# BLE_V_1_0.net
KiCad netlist of a schematic drawn in EAGLE
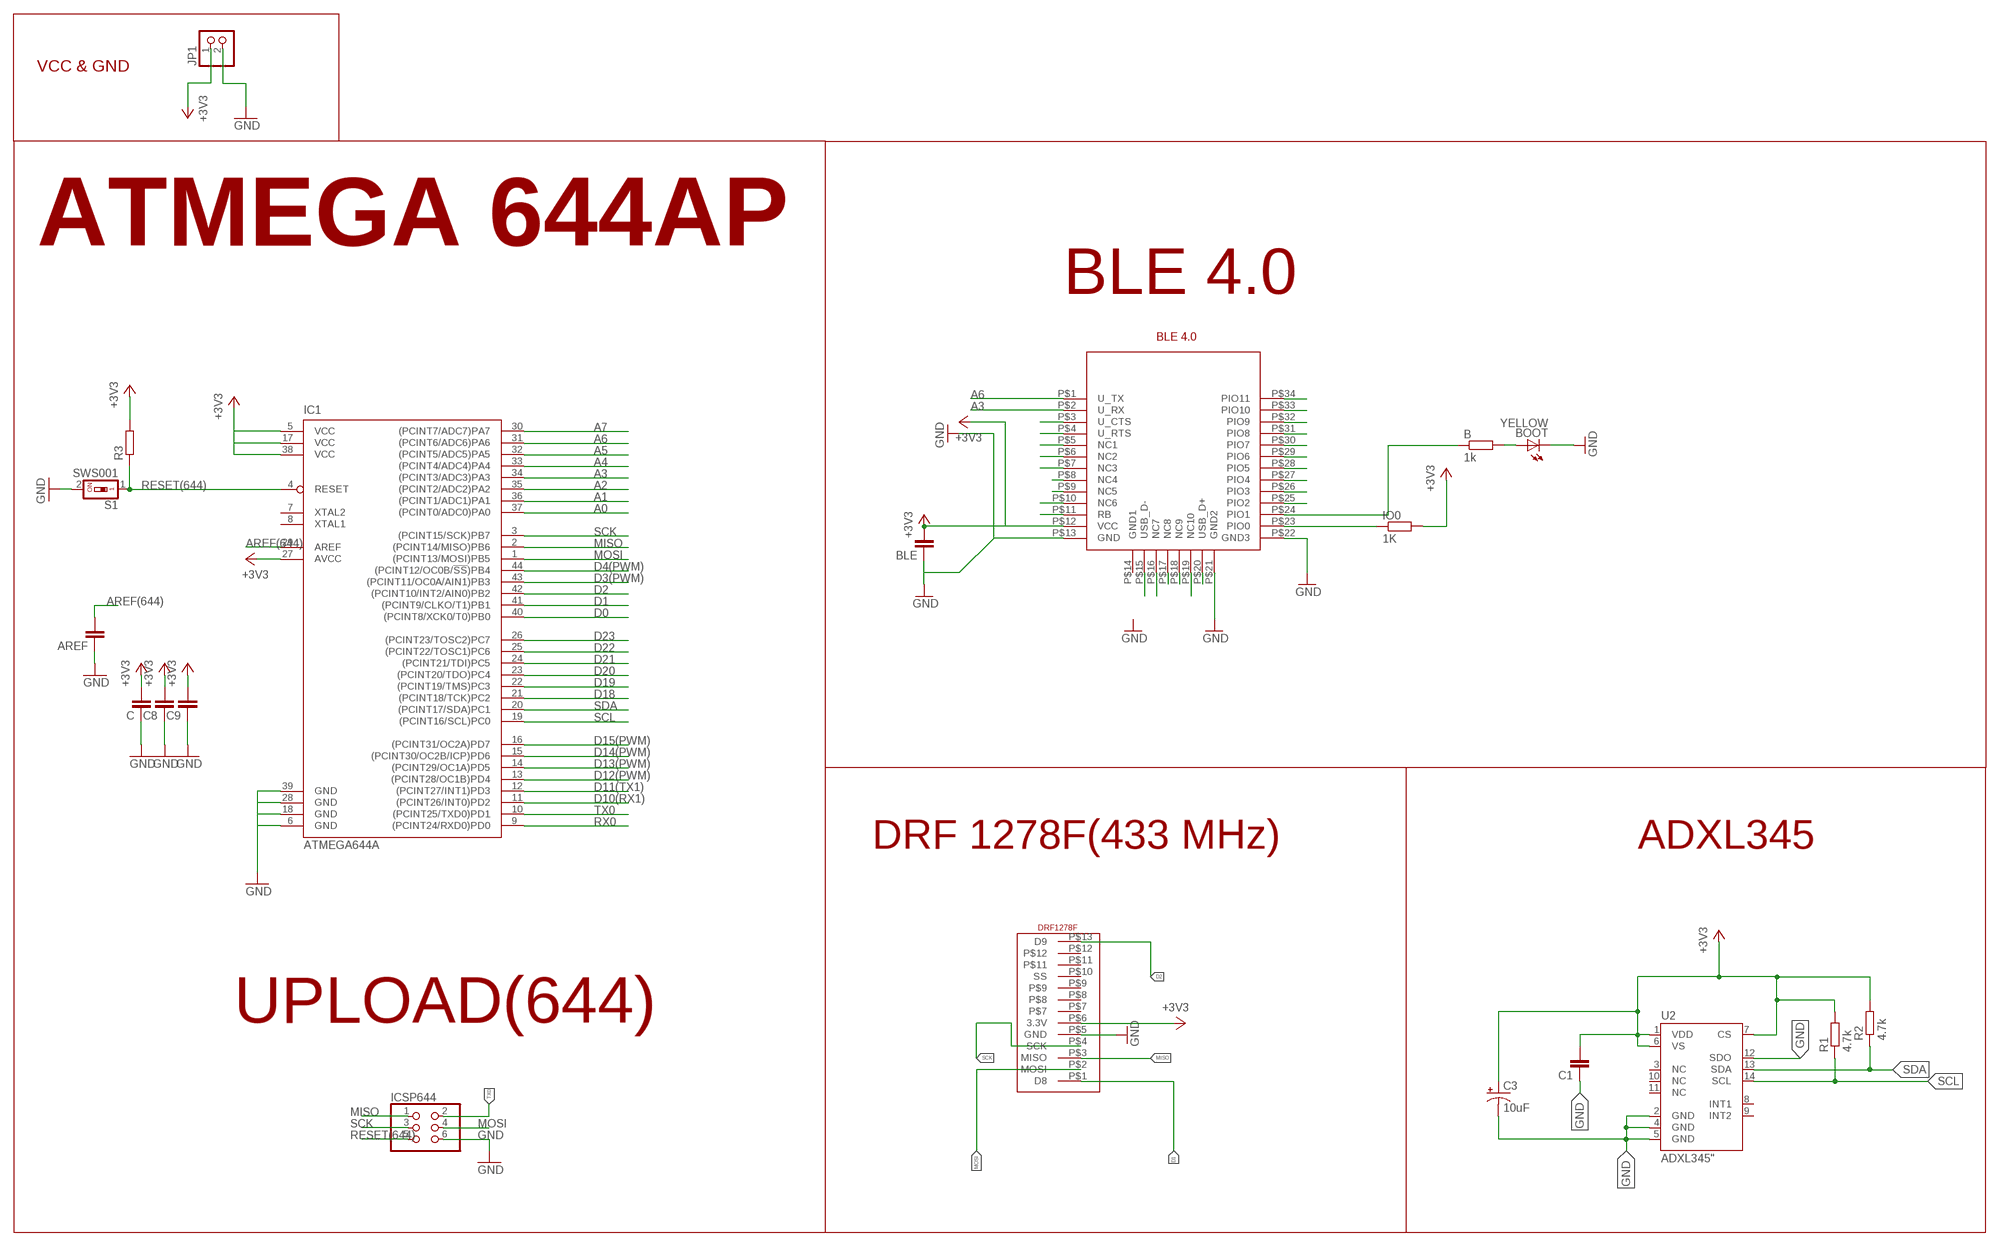
[diagram p0: schematic, sheet 1]

(export (version "E")
  (design (tool "Eeschema 10.0.6"))
  (components
    (comp (ref "AREF")
      (value "100nF")
      (footprint "eagle-import:C0805")
      (libsource (lib "eagle-import") (part "C-EUC0805"))
    )
    (comp (ref "B")
      (value "1k")
      (footprint "eagle-import:R0805")
      (libsource (lib "eagle-import") (part "R-EU_R0805"))
    )
    (comp (ref "BLE")
      (value "100nF")
      (footprint "eagle-import:C0805")
      (libsource (lib "eagle-import") (part "C-EUC0805"))
    )
    (comp (ref "BOOT")
      (value "YELLOW")
      (footprint "eagle-import:CHIP-LED0805")
      (libsource (lib "eagle-import") (part "LEDCHIP-LED0805"))
    )
    (comp (ref "C")
      (value "22 uF")
      (footprint "eagle-import:C0805")
      (libsource (lib "eagle-import") (part "C-EUC0805"))
    )
    (comp (ref "C1")
      (value "0.1uF")
      (footprint "eagle-import:C0805")
      (libsource (lib "eagle-import") (part "C-EUC0805"))
    )
    (comp (ref "C3")
      (value "10uF")
      (footprint "eagle-import:EIA3216")
      (libsource (lib "eagle-import") (part "CAP_POL1206"))
    )
    (comp (ref "C8")
      (value "100nF")
      (footprint "eagle-import:C0805")
      (libsource (lib "eagle-import") (part "C-EUC0805"))
    )
    (comp (ref "C9")
      (value "100nF")
      (footprint "eagle-import:C0805")
      (libsource (lib "eagle-import") (part "C-EUC0805"))
    )
    (comp (ref "IC1")
      (value "ATMEGA644A")
      (footprint "eagle-import:TQFP44")
      (fields (field (name "MPN") "ATMEGA644PV-10AU"))
      (libsource (lib "eagle-import") (part "ATMEGA644A"))
    )
    (comp (ref "ICSP644")
      (value "PINHD-2X3")
      (footprint "eagle-import:2X03")
      (libsource (lib "eagle-import") (part "PINHD-2X3"))
    )
    (comp (ref "IO0")
      (value "1K")
      (footprint "eagle-import:R0805")
      (libsource (lib "eagle-import") (part "R-EU_R0805"))
    )
    (comp (ref "JP1")
      (value "PINHD-1X2")
      (footprint "eagle-import:1X02")
      (libsource (lib "eagle-import") (part "PINHD-1X2"))
    )
    (comp (ref "R1")
      (value "4.7k")
      (footprint "eagle-import:R0805")
      (libsource (lib "eagle-import") (part "R-EU_R0805"))
    )
    (comp (ref "R2")
      (value "4.7k")
      (footprint "eagle-import:R0805")
      (libsource (lib "eagle-import") (part "R-EU_R0805"))
    )
    (comp (ref "R3")
      (value "R-EU_R0805")
      (footprint "eagle-import:R0805")
      (libsource (lib "eagle-import") (part "R-EU_R0805"))
    )
    (comp (ref "S1")
      (value "SWS001")
      (footprint "eagle-import:SMS-001")
      (libsource (lib "eagle-import") (part "SWS001"))
    )
    (comp (ref "U$1")
      (value "DRF1278F")
      (footprint "eagle-import:DIP13")
      (libsource (lib "eagle-import") (part "DRF1278F"))
    )
    (comp (ref "U$6")
      (value "BLUETOOTH_4.0(13)")
      (footprint "eagle-import:BLUTOOTH_4.0(13)")
      (libsource (lib "eagle-import") (part "BLUETOOTH_4.0(13)"))
    )
    (comp (ref "U2")
      (value "ADXL345\"")
      (footprint "eagle-import:ADXL3451_1")
      (libsource (lib "eagle-import") (part "ADXL345{dblquote}"))
    )
  )
  (nets
    (net (code "1") (name "+3V3") (class "Default")
      (node (ref "BLE") (pin "2") (pinfunction "2_2") (pintype "passive"))
      (node (ref "C") (pin "2") (pinfunction "2_2") (pintype "passive"))
      (node (ref "C1") (pin "2") (pinfunction "2_2") (pintype "passive"))
      (node (ref "C3") (pin "A") (pinfunction "+_A") (pintype "passive"))
      (node (ref "C8") (pin "2") (pinfunction "2_2") (pintype "passive"))
      (node (ref "C9") (pin "2") (pinfunction "2_2") (pintype "passive"))
      (node (ref "IC1") (pin "17") (pinfunction "VCC_17") (pintype "power_in"))
      (node (ref "IC1") (pin "27") (pinfunction "AVCC_27") (pintype "power_in"))
      (node (ref "IC1") (pin "38") (pinfunction "VCC_38") (pintype "power_in"))
      (node (ref "IC1") (pin "5") (pinfunction "VCC_5") (pintype "power_in"))
      (node (ref "IO0") (pin "2") (pinfunction "2_2") (pintype "passive"))
      (node (ref "JP1") (pin "1") (pinfunction "1_1") (pintype "passive"))
      (node (ref "R1") (pin "2") (pinfunction "2_2") (pintype "passive"))
      (node (ref "R2") (pin "2") (pinfunction "2_2") (pintype "passive"))
      (node (ref "R3") (pin "2") (pinfunction "2_2") (pintype "passive"))
      (node (ref "U$1") (pin "P$6") (pinfunction "3.3V_P$6") (pintype "bidirectional"))
      (node (ref "U$6") (pin "P$12") (pinfunction "VCC_P$12") (pintype "bidirectional"))
      (node (ref "U2") (pin "1") (pinfunction "VDD_1") (pintype "bidirectional"))
      (node (ref "U2") (pin "6") (pinfunction "VS_6") (pintype "bidirectional"))
      (node (ref "U2") (pin "7") (pinfunction "CS_7") (pintype "bidirectional"))
    )
    (net (code "2") (name "/A0") (class "Default")
      (node (ref "IC1") (pin "37") (pinfunction "(PCINT0/ADC0)PA0_37") (pintype "bidirectional"))
    )
    (net (code "3") (name "/A1") (class "Default")
      (node (ref "IC1") (pin "36") (pinfunction "(PCINT1/ADC1)PA1_36") (pintype "bidirectional"))
    )
    (net (code "4") (name "/A2") (class "Default")
      (node (ref "IC1") (pin "35") (pinfunction "(PCINT2/ADC2)PA2_35") (pintype "bidirectional"))
    )
    (net (code "5") (name "/A3") (class "Default")
      (node (ref "IC1") (pin "34") (pinfunction "(PCINT3/ADC3)PA3_34") (pintype "bidirectional"))
      (node (ref "U$6") (pin "P$2") (pinfunction "U_RX_P$2") (pintype "bidirectional"))
    )
    (net (code "6") (name "/A4") (class "Default")
      (node (ref "IC1") (pin "33") (pinfunction "(PCINT4/ADC4)PA4_33") (pintype "bidirectional"))
    )
    (net (code "7") (name "/A5") (class "Default")
      (node (ref "IC1") (pin "32") (pinfunction "(PCINT5/ADC5)PA5_32") (pintype "bidirectional"))
    )
    (net (code "8") (name "/A6") (class "Default")
      (node (ref "IC1") (pin "31") (pinfunction "(PCINT6/ADC6)PA6_31") (pintype "bidirectional"))
      (node (ref "U$6") (pin "P$1") (pinfunction "U_TX_P$1") (pintype "bidirectional"))
    )
    (net (code "9") (name "/A7") (class "Default")
      (node (ref "IC1") (pin "30") (pinfunction "(PCINT7/ADC7)PA7_30") (pintype "bidirectional"))
    )
    (net (code "10") (name "/AREF(644)") (class "Default")
      (node (ref "AREF") (pin "2") (pinfunction "2_2") (pintype "passive"))
      (node (ref "IC1") (pin "29") (pinfunction "AREF_29") (pintype "passive"))
    )
    (net (code "11") (name "/D0") (class "Default")
      (node (ref "IC1") (pin "40") (pinfunction "(PCINT8/XCK0/T0)PB0_40") (pintype "bidirectional"))
    )
    (net (code "12") (name "/D3(PWM)") (class "Default")
      (node (ref "IC1") (pin "43") (pinfunction "(PCINT11/OC0A/AIN1)PB3_43") (pintype "bidirectional"))
    )
    (net (code "13") (name "/D4(PWM)") (class "Default")
      (node (ref "IC1") (pin "44") (pinfunction "(PCINT12/OC0B/~{SS})PB4_44") (pintype "bidirectional"))
    )
    (net (code "14") (name "/D10(RX1)") (class "Default")
      (node (ref "IC1") (pin "11") (pinfunction "(PCINT26/INT0)PD2_11") (pintype "bidirectional"))
    )
    (net (code "15") (name "/D11(TX1)") (class "Default")
      (node (ref "IC1") (pin "12") (pinfunction "(PCINT27/INT1)PD3_12") (pintype "bidirectional"))
    )
    (net (code "16") (name "/D12(PWM)") (class "Default")
      (node (ref "IC1") (pin "13") (pinfunction "(PCINT28/OC1B)PD4_13") (pintype "bidirectional"))
    )
    (net (code "17") (name "/D13(PWM)") (class "Default")
      (node (ref "IC1") (pin "14") (pinfunction "(PCINT29/OC1A)PD5_14") (pintype "bidirectional"))
    )
    (net (code "18") (name "/D14(PWM)") (class "Default")
      (node (ref "IC1") (pin "15") (pinfunction "(PCINT30/OC2B/ICP)PD6_15") (pintype "bidirectional"))
    )
    (net (code "19") (name "/D15(PWM)") (class "Default")
      (node (ref "IC1") (pin "16") (pinfunction "(PCINT31/OC2A)PD7_16") (pintype "bidirectional"))
    )
    (net (code "20") (name "/D18") (class "Default")
      (node (ref "IC1") (pin "21") (pinfunction "(PCINT18/TCK)PC2_21") (pintype "output"))
    )
    (net (code "21") (name "/D19") (class "Default")
      (node (ref "IC1") (pin "22") (pinfunction "(PCINT19/TMS)PC3_22") (pintype "output"))
    )
    (net (code "22") (name "/D20") (class "Default")
      (node (ref "IC1") (pin "23") (pinfunction "(PCINT20/TDO)PC4_23") (pintype "output"))
    )
    (net (code "23") (name "/D21") (class "Default")
      (node (ref "IC1") (pin "24") (pinfunction "(PCINT21/TDI)PC5_24") (pintype "output"))
    )
    (net (code "24") (name "/D22") (class "Default")
      (node (ref "IC1") (pin "25") (pinfunction "(PCINT22/TOSC1)PC6_25") (pintype "output"))
    )
    (net (code "25") (name "/D23") (class "Default")
      (node (ref "IC1") (pin "26") (pinfunction "(PCINT23/TOSC2)PC7_26") (pintype "output"))
    )
    (net (code "26") (name "/RESET(644)") (class "Default")
      (node (ref "IC1") (pin "4") (pinfunction "RESET_4") (pintype "input"))
      (node (ref "ICSP644") (pin "5") (pinfunction "5_5") (pintype "passive"))
      (node (ref "R3") (pin "1") (pinfunction "1_1") (pintype "passive"))
      (node (ref "S1") (pin "1") (pinfunction "1_1") (pintype "passive"))
    )
    (net (code "27") (name "/RX0") (class "Default")
      (node (ref "IC1") (pin "9") (pinfunction "(PCINT24/RXD0)PD0_9") (pintype "bidirectional"))
    )
    (net (code "28") (name "D1") (class "Default")
      (node (ref "IC1") (pin "41") (pinfunction "(PCINT9/CLKO/T1)PB1_41") (pintype "bidirectional"))
      (node (ref "U$1") (pin "P$1") (pinfunction "D8_P$1") (pintype "bidirectional"))
    )
    (net (code "29") (name "D2") (class "Default")
      (node (ref "IC1") (pin "42") (pinfunction "(PCINT10/INT2/AIN0)PB2_42") (pintype "bidirectional"))
      (node (ref "U$1") (pin "P$13") (pinfunction "D9_P$13") (pintype "bidirectional"))
    )
    (net (code "30") (name "GND") (class "Default")
      (node (ref "AREF") (pin "1") (pinfunction "1_1") (pintype "passive"))
      (node (ref "BLE") (pin "1") (pinfunction "1_1") (pintype "passive"))
      (node (ref "BOOT") (pin "C") (pinfunction "C_C") (pintype "passive"))
      (node (ref "C") (pin "1") (pinfunction "1_1") (pintype "passive"))
      (node (ref "C1") (pin "1") (pinfunction "1_1") (pintype "passive"))
      (node (ref "C3") (pin "C") (pinfunction "-_C") (pintype "passive"))
      (node (ref "C8") (pin "1") (pinfunction "1_1") (pintype "passive"))
      (node (ref "C9") (pin "1") (pinfunction "1_1") (pintype "passive"))
      (node (ref "IC1") (pin "18") (pinfunction "GND_18") (pintype "power_in"))
      (node (ref "IC1") (pin "28") (pinfunction "GND_28") (pintype "power_in"))
      (node (ref "IC1") (pin "39") (pinfunction "GND_39") (pintype "power_in"))
      (node (ref "IC1") (pin "6") (pinfunction "GND_6") (pintype "power_in"))
      (node (ref "ICSP644") (pin "6") (pinfunction "6_6") (pintype "passive"))
      (node (ref "JP1") (pin "2") (pinfunction "2_2") (pintype "passive"))
      (node (ref "S1") (pin "2") (pinfunction "2_2") (pintype "passive"))
      (node (ref "U$1") (pin "P$5") (pinfunction "GND_P$5") (pintype "bidirectional"))
      (node (ref "U$6") (pin "P$13") (pinfunction "GND_P$13") (pintype "bidirectional"))
      (node (ref "U$6") (pin "P$21") (pinfunction "GND2_P$21") (pintype "bidirectional"))
      (node (ref "U$6") (pin "P$22") (pinfunction "GND3_P$22") (pintype "bidirectional"))
      (node (ref "U2") (pin "12") (pinfunction "SDO_12") (pintype "bidirectional"))
      (node (ref "U2") (pin "2") (pinfunction "GND_2") (pintype "bidirectional"))
      (node (ref "U2") (pin "4") (pinfunction "GND_4") (pintype "bidirectional"))
      (node (ref "U2") (pin "5") (pinfunction "GND_5") (pintype "bidirectional"))
    )
    (net (code "31") (name "MISO") (class "Default")
      (node (ref "IC1") (pin "2") (pinfunction "(PCINT14/MISO)PB6_2") (pintype "bidirectional"))
      (node (ref "ICSP644") (pin "1") (pinfunction "1_1") (pintype "passive"))
      (node (ref "U$1") (pin "P$3") (pinfunction "MISO_P$3") (pintype "bidirectional"))
    )
    (net (code "32") (name "MOSI") (class "Default")
      (node (ref "IC1") (pin "1") (pinfunction "(PCINT13/MOSI)PB5_1") (pintype "bidirectional"))
      (node (ref "ICSP644") (pin "4") (pinfunction "4_4") (pintype "passive"))
      (node (ref "U$1") (pin "P$2") (pinfunction "MOSI_P$2") (pintype "bidirectional"))
    )
    (net (code "33") (name "Net-(B-Pad2)") (class "Default")
      (node (ref "B") (pin "2") (pinfunction "2_2") (pintype "passive"))
      (node (ref "BOOT") (pin "A") (pinfunction "A_A") (pintype "passive"))
    )
    (net (code "34") (name "Net-(U$6-PIO0)") (class "Default")
      (node (ref "IO0") (pin "1") (pinfunction "1_1") (pintype "passive"))
      (node (ref "U$6") (pin "P$23") (pinfunction "PIO0_P$23") (pintype "bidirectional"))
    )
    (net (code "35") (name "Net-(U$6-PIO1)") (class "Default")
      (node (ref "B") (pin "1") (pinfunction "1_1") (pintype "passive"))
      (node (ref "U$6") (pin "P$24") (pinfunction "PIO1_P$24") (pintype "bidirectional"))
    )
    (net (code "36") (name "SCK") (class "Default")
      (node (ref "IC1") (pin "3") (pinfunction "(PCINT15/SCK)PB7_3") (pintype "bidirectional"))
      (node (ref "ICSP644") (pin "3") (pinfunction "3_3") (pintype "passive"))
      (node (ref "U$1") (pin "P$4") (pinfunction "SCK_P$4") (pintype "bidirectional"))
    )
    (net (code "37") (name "SCL") (class "Default")
      (node (ref "IC1") (pin "19") (pinfunction "(PCINT16/SCL)PC0_19") (pintype "output"))
      (node (ref "R1") (pin "1") (pinfunction "1_1") (pintype "passive"))
      (node (ref "U2") (pin "14") (pinfunction "SCL_14") (pintype "bidirectional"))
    )
    (net (code "38") (name "SDA") (class "Default")
      (node (ref "IC1") (pin "20") (pinfunction "(PCINT17/SDA)PC1_20") (pintype "output"))
      (node (ref "R2") (pin "1") (pinfunction "1_1") (pintype "passive"))
      (node (ref "U2") (pin "13") (pinfunction "SDA_13") (pintype "bidirectional"))
    )
    (net (code "39") (name "TX0") (class "Default")
      (node (ref "IC1") (pin "10") (pinfunction "(PCINT25/TXD0)PD1_10") (pintype "bidirectional"))
      (node (ref "ICSP644") (pin "2") (pinfunction "2_2") (pintype "passive"))
    )
    (net (code "40") (name "unconnected-(IC1-XTAL1-Pad8)") (class "Default")
      (node (ref "IC1") (pin "8") (pinfunction "XTAL1_8") (pintype "bidirectional"))
    )
    (net (code "41") (name "unconnected-(IC1-XTAL2-Pad7)") (class "Default")
      (node (ref "IC1") (pin "7") (pinfunction "XTAL2_7") (pintype "bidirectional"))
    )
    (net (code "42") (name "unconnected-(U$1-PadP$7)") (class "Default")
      (node (ref "U$1") (pin "P$7") (pinfunction "P$7_P$7") (pintype "bidirectional"))
    )
    (net (code "43") (name "unconnected-(U$1-PadP$8)") (class "Default")
      (node (ref "U$1") (pin "P$8") (pinfunction "P$8_P$8") (pintype "bidirectional"))
    )
    (net (code "44") (name "unconnected-(U$1-PadP$9)") (class "Default")
      (node (ref "U$1") (pin "P$9") (pinfunction "P$9_P$9") (pintype "bidirectional"))
    )
    (net (code "45") (name "unconnected-(U$1-PadP$11)") (class "Default")
      (node (ref "U$1") (pin "P$11") (pinfunction "P$11_P$11") (pintype "bidirectional"))
    )
    (net (code "46") (name "unconnected-(U$1-PadP$12)") (class "Default")
      (node (ref "U$1") (pin "P$12") (pinfunction "P$12_P$12") (pintype "bidirectional"))
    )
    (net (code "47") (name "unconnected-(U$1-SS-PadP$10)") (class "Default")
      (node (ref "U$1") (pin "P$10") (pinfunction "SS_P$10") (pintype "bidirectional"))
    )
    (net (code "48") (name "unconnected-(U$6-GND1-PadP$14)") (class "Default")
      (node (ref "U$6") (pin "P$14") (pinfunction "GND1_P$14") (pintype "bidirectional"))
    )
    (net (code "49") (name "unconnected-(U$6-NC1-PadP$5)") (class "Default")
      (node (ref "U$6") (pin "P$5") (pinfunction "NC1_P$5") (pintype "bidirectional"))
    )
    (net (code "50") (name "unconnected-(U$6-NC2-PadP$6)") (class "Default")
      (node (ref "U$6") (pin "P$6") (pinfunction "NC2_P$6") (pintype "bidirectional"))
    )
    (net (code "51") (name "unconnected-(U$6-NC3-PadP$7)") (class "Default")
      (node (ref "U$6") (pin "P$7") (pinfunction "NC3_P$7") (pintype "bidirectional"))
    )
    (net (code "52") (name "unconnected-(U$6-NC4-PadP$8)") (class "Default")
      (node (ref "U$6") (pin "P$8") (pinfunction "NC4_P$8") (pintype "bidirectional"))
    )
    (net (code "53") (name "unconnected-(U$6-NC5-PadP$9)") (class "Default")
      (node (ref "U$6") (pin "P$9") (pinfunction "NC5_P$9") (pintype "bidirectional"))
    )
    (net (code "54") (name "unconnected-(U$6-NC6-PadP$10)") (class "Default")
      (node (ref "U$6") (pin "P$10") (pinfunction "NC6_P$10") (pintype "bidirectional"))
    )
    (net (code "55") (name "unconnected-(U$6-NC7-PadP$16)") (class "Default")
      (node (ref "U$6") (pin "P$16") (pinfunction "NC7_P$16") (pintype "bidirectional"))
    )
    (net (code "56") (name "unconnected-(U$6-NC8-PadP$17)") (class "Default")
      (node (ref "U$6") (pin "P$17") (pinfunction "NC8_P$17") (pintype "bidirectional"))
    )
    (net (code "57") (name "unconnected-(U$6-NC9-PadP$18)") (class "Default")
      (node (ref "U$6") (pin "P$18") (pinfunction "NC9_P$18") (pintype "bidirectional"))
    )
    (net (code "58") (name "unconnected-(U$6-NC10-PadP$19)") (class "Default")
      (node (ref "U$6") (pin "P$19") (pinfunction "NC10_P$19") (pintype "bidirectional"))
    )
    (net (code "59") (name "unconnected-(U$6-PIO2-PadP$25)") (class "Default")
      (node (ref "U$6") (pin "P$25") (pinfunction "PIO2_P$25") (pintype "bidirectional"))
    )
    (net (code "60") (name "unconnected-(U$6-PIO3-PadP$26)") (class "Default")
      (node (ref "U$6") (pin "P$26") (pinfunction "PIO3_P$26") (pintype "bidirectional"))
    )
    (net (code "61") (name "unconnected-(U$6-PIO4-PadP$27)") (class "Default")
      (node (ref "U$6") (pin "P$27") (pinfunction "PIO4_P$27") (pintype "bidirectional"))
    )
    (net (code "62") (name "unconnected-(U$6-PIO5-PadP$28)") (class "Default")
      (node (ref "U$6") (pin "P$28") (pinfunction "PIO5_P$28") (pintype "bidirectional"))
    )
    (net (code "63") (name "unconnected-(U$6-PIO6-PadP$29)") (class "Default")
      (node (ref "U$6") (pin "P$29") (pinfunction "PIO6_P$29") (pintype "bidirectional"))
    )
    (net (code "64") (name "unconnected-(U$6-PIO7-PadP$30)") (class "Default")
      (node (ref "U$6") (pin "P$30") (pinfunction "PIO7_P$30") (pintype "bidirectional"))
    )
    (net (code "65") (name "unconnected-(U$6-PIO8-PadP$31)") (class "Default")
      (node (ref "U$6") (pin "P$31") (pinfunction "PIO8_P$31") (pintype "bidirectional"))
    )
    (net (code "66") (name "unconnected-(U$6-PIO9-PadP$32)") (class "Default")
      (node (ref "U$6") (pin "P$32") (pinfunction "PIO9_P$32") (pintype "bidirectional"))
    )
    (net (code "67") (name "unconnected-(U$6-PIO10-PadP$33)") (class "Default")
      (node (ref "U$6") (pin "P$33") (pinfunction "PIO10_P$33") (pintype "bidirectional"))
    )
    (net (code "68") (name "unconnected-(U$6-PIO11-PadP$34)") (class "Default")
      (node (ref "U$6") (pin "P$34") (pinfunction "PIO11_P$34") (pintype "bidirectional"))
    )
    (net (code "69") (name "unconnected-(U$6-RB-PadP$11)") (class "Default")
      (node (ref "U$6") (pin "P$11") (pinfunction "RB_P$11") (pintype "bidirectional"))
    )
    (net (code "70") (name "unconnected-(U$6-USB_D+-PadP$20)") (class "Default")
      (node (ref "U$6") (pin "P$20") (pinfunction "USB_D+_P$20") (pintype "bidirectional"))
    )
    (net (code "71") (name "unconnected-(U$6-USB_D--PadP$15)") (class "Default")
      (node (ref "U$6") (pin "P$15") (pinfunction "USB_D-_P$15") (pintype "bidirectional"))
    )
    (net (code "72") (name "unconnected-(U$6-U_CTS-PadP$3)") (class "Default")
      (node (ref "U$6") (pin "P$3") (pinfunction "U_CTS_P$3") (pintype "bidirectional"))
    )
    (net (code "73") (name "unconnected-(U$6-U_RTS-PadP$4)") (class "Default")
      (node (ref "U$6") (pin "P$4") (pinfunction "U_RTS_P$4") (pintype "bidirectional"))
    )
    (net (code "74") (name "unconnected-(U2-INT1-Pad8)") (class "Default")
      (node (ref "U2") (pin "8") (pinfunction "INT1_8") (pintype "bidirectional"))
    )
    (net (code "75") (name "unconnected-(U2-INT2-Pad9)") (class "Default")
      (node (ref "U2") (pin "9") (pinfunction "INT2_9") (pintype "bidirectional"))
    )
    (net (code "76") (name "unconnected-(U2-NC-Pad3)") (class "Default")
      (node (ref "U2") (pin "3") (pinfunction "NC_3") (pintype "bidirectional"))
    )
    (net (code "77") (name "unconnected-(U2-NC-Pad10)") (class "Default")
      (node (ref "U2") (pin "10") (pinfunction "NC_10") (pintype "bidirectional"))
    )
    (net (code "78") (name "unconnected-(U2-NC-Pad11)") (class "Default")
      (node (ref "U2") (pin "11") (pinfunction "NC_11") (pintype "bidirectional"))
    )
  )
)
